# Mergen_Telemetri_Ate_leme.net
KiCad netlist of a schematic drawn in EAGLE
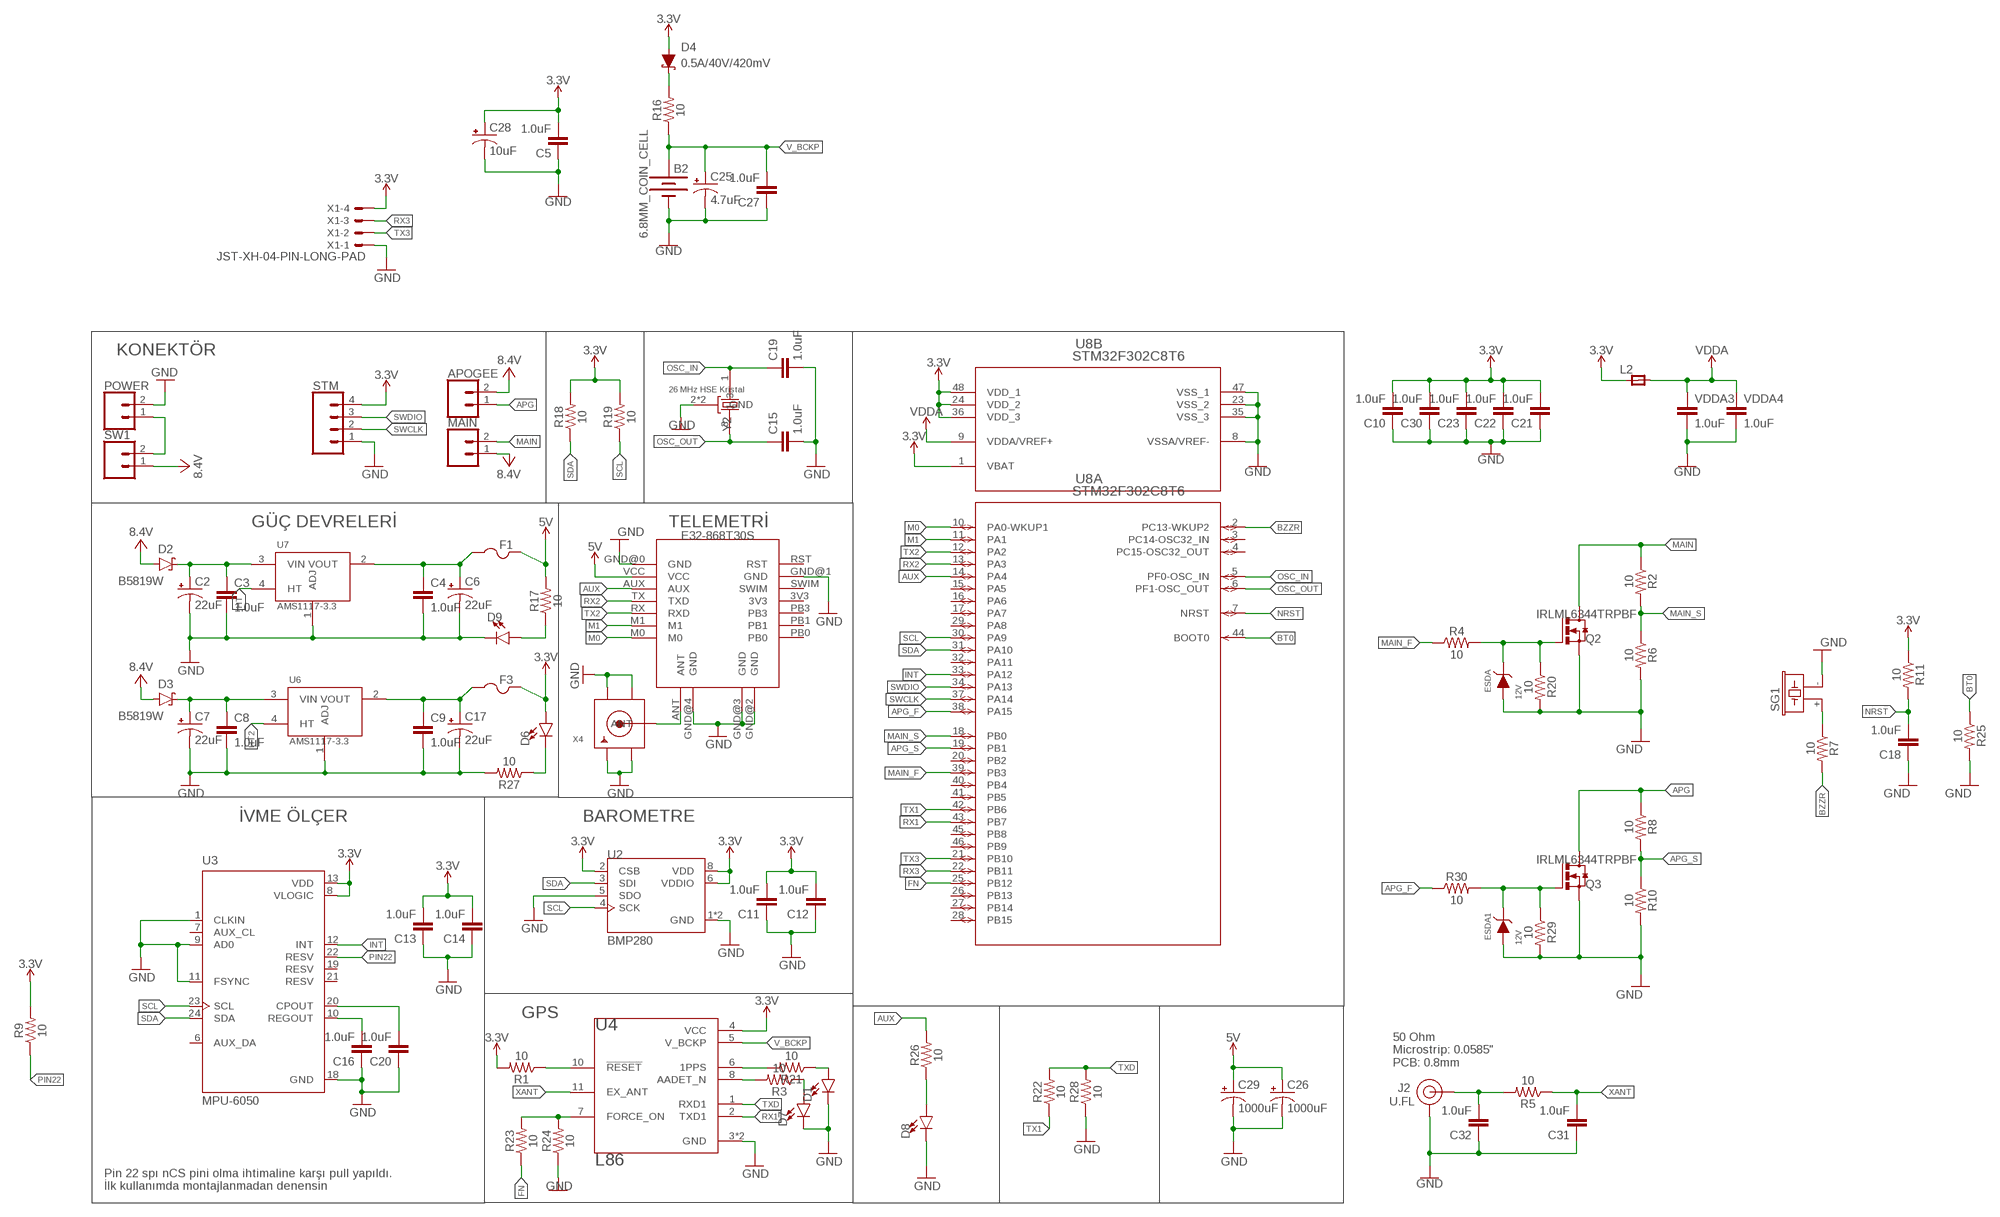
[diagram p0: schematic, sheet 1]

(export (version "E")
  (design (tool "Eeschema 10.0.6"))
  (components
    (comp (ref "APOGEE")
      (value "CONN_023.5MM-NO_SILK")
      (footprint "eagle-import:SCREWTERMINAL-3.5MM-2-NS")
      (libsource (lib "eagle-import") (part "CONN_023.5MM-NO_SILK"))
    )
    (comp (ref "B2")
      (value "6.8MM_COIN_CELL")
      (footprint "eagle-import:BATTCON-6.8MM")
      (libsource (lib "eagle-import") (part "BATTERY-6.8MM_SMD"))
    )
    (comp (ref "C2")
      (value "22uF")
      (footprint "eagle-import:EIA3528")
      (libsource (lib "eagle-import") (part "47UF-POLAR-EIA3528-10V-10%"))
    )
    (comp (ref "C3")
      (value "1.0uF")
      (footprint "eagle-import:1206")
      (libsource (lib "eagle-import") (part "1.0UF-1206-50V-10%"))
    )
    (comp (ref "C4")
      (value "1.0uF")
      (footprint "eagle-import:1206")
      (libsource (lib "eagle-import") (part "1.0UF-1206-50V-10%"))
    )
    (comp (ref "C5")
      (value "1.0uF")
      (footprint "eagle-import:1206")
      (libsource (lib "eagle-import") (part "1.0UF-1206-50V-10%"))
    )
    (comp (ref "C6")
      (value "22uF")
      (footprint "eagle-import:EIA3528")
      (libsource (lib "eagle-import") (part "47UF-POLAR-EIA3528-10V-10%"))
    )
    (comp (ref "C7")
      (value "22uF")
      (footprint "eagle-import:EIA3528")
      (libsource (lib "eagle-import") (part "47UF-POLAR-EIA3528-10V-10%"))
    )
    (comp (ref "C8")
      (value "1.0uF")
      (footprint "eagle-import:1206")
      (libsource (lib "eagle-import") (part "1.0UF-1206-50V-10%"))
    )
    (comp (ref "C9")
      (value "1.0uF")
      (footprint "eagle-import:1206")
      (libsource (lib "eagle-import") (part "1.0UF-1206-50V-10%"))
    )
    (comp (ref "C10")
      (value "1.0uF")
      (footprint "eagle-import:1206")
      (libsource (lib "eagle-import") (part "1.0UF-1206-50V-10%"))
    )
    (comp (ref "C11")
      (value "1.0uF")
      (footprint "eagle-import:1206")
      (libsource (lib "eagle-import") (part "1.0UF-1206-50V-10%"))
    )
    (comp (ref "C12")
      (value "1.0uF")
      (footprint "eagle-import:1206")
      (libsource (lib "eagle-import") (part "1.0UF-1206-50V-10%"))
    )
    (comp (ref "C13")
      (value "1.0uF")
      (footprint "eagle-import:1206")
      (libsource (lib "eagle-import") (part "1.0UF-1206-50V-10%"))
    )
    (comp (ref "C14")
      (value "1.0uF")
      (footprint "eagle-import:1206")
      (libsource (lib "eagle-import") (part "1.0UF-1206-50V-10%"))
    )
    (comp (ref "C15")
      (value "1.0uF")
      (footprint "eagle-import:1206")
      (libsource (lib "eagle-import") (part "1.0UF-1206-50V-10%"))
    )
    (comp (ref "C16")
      (value "1.0uF")
      (footprint "eagle-import:1206")
      (libsource (lib "eagle-import") (part "1.0UF-1206-50V-10%"))
    )
    (comp (ref "C17")
      (value "22uF")
      (footprint "eagle-import:EIA3528")
      (libsource (lib "eagle-import") (part "47UF-POLAR-EIA3528-10V-10%"))
    )
    (comp (ref "C18")
      (value "1.0uF")
      (footprint "eagle-import:1206")
      (libsource (lib "eagle-import") (part "1.0UF-1206-50V-10%"))
    )
    (comp (ref "C19")
      (value "1.0uF")
      (footprint "eagle-import:1206")
      (libsource (lib "eagle-import") (part "1.0UF-1206-50V-10%"))
    )
    (comp (ref "C20")
      (value "1.0uF")
      (footprint "eagle-import:1206")
      (libsource (lib "eagle-import") (part "1.0UF-1206-50V-10%"))
    )
    (comp (ref "C21")
      (value "1.0uF")
      (footprint "eagle-import:1206")
      (libsource (lib "eagle-import") (part "1.0UF-1206-50V-10%"))
    )
    (comp (ref "C22")
      (value "1.0uF")
      (footprint "eagle-import:1206")
      (libsource (lib "eagle-import") (part "1.0UF-1206-50V-10%"))
    )
    (comp (ref "C23")
      (value "1.0uF")
      (footprint "eagle-import:1206")
      (libsource (lib "eagle-import") (part "1.0UF-1206-50V-10%"))
    )
    (comp (ref "C25")
      (value "4.7uF")
      (footprint "eagle-import:EIA3528")
      (libsource (lib "eagle-import") (part "47UF-POLAR-EIA3528-10V-10%"))
    )
    (comp (ref "C26")
      (value "1000uF")
      (footprint "eagle-import:150CLZ-1010")
      (libsource (lib "eagle-import") (part "CPOL-US150CLZ-1010"))
    )
    (comp (ref "C27")
      (value "1.0uF")
      (footprint "eagle-import:1206")
      (libsource (lib "eagle-import") (part "1.0UF-1206-50V-10%"))
    )
    (comp (ref "C28")
      (value "10uF")
      (footprint "eagle-import:EIA3528")
      (libsource (lib "eagle-import") (part "47UF-POLAR-EIA3528-10V-10%"))
    )
    (comp (ref "C29")
      (value "1000uF")
      (footprint "eagle-import:150CLZ-1010")
      (libsource (lib "eagle-import") (part "CPOL-US150CLZ-1010"))
    )
    (comp (ref "C30")
      (value "1.0uF")
      (footprint "eagle-import:1206")
      (libsource (lib "eagle-import") (part "1.0UF-1206-50V-10%"))
    )
    (comp (ref "C31")
      (value "1.0uF")
      (footprint "eagle-import:1206")
      (libsource (lib "eagle-import") (part "1.0UF-1206-50V-10%"))
    )
    (comp (ref "C32")
      (value "1.0uF")
      (footprint "eagle-import:1206")
      (libsource (lib "eagle-import") (part "1.0UF-1206-50V-10%"))
    )
    (comp (ref "D1")
      (value "LED1206")
      (footprint "eagle-import:LED-1206")
      (libsource (lib "eagle-import") (part "LED1206"))
    )
    (comp (ref "D2")
      (value "B5819W")
      (footprint "eagle-import:SODFL3718X115")
      (fields (field (name "MANUFACTURER") "ON Semiconductor") (field (name "MPN") "MBR0520LT1G"))
      (libsource (lib "eagle-import") (part "SCHOTTKY_DO-219MBR0520LT1G"))
    )
    (comp (ref "D3")
      (value "B5819W")
      (footprint "eagle-import:SODFL3718X115")
      (fields (field (name "MANUFACTURER") "ON Semiconductor") (field (name "MPN") "MBR0520LT1G"))
      (libsource (lib "eagle-import") (part "SCHOTTKY_DO-219MBR0520LT1G"))
    )
    (comp (ref "D4")
      (value "0.5A/40V/420mV")
      (footprint "eagle-import:SOD-323")
      (libsource (lib "eagle-import") (part "DIODE-SCHOTTKY-PMEG4005EJ"))
    )
    (comp (ref "D6")
      (value "LED1206")
      (footprint "eagle-import:LED-1206")
      (libsource (lib "eagle-import") (part "LED1206"))
    )
    (comp (ref "D7")
      (value "LED1206")
      (footprint "eagle-import:LED-1206")
      (libsource (lib "eagle-import") (part "LED1206"))
    )
    (comp (ref "D8")
      (value "LED1206")
      (footprint "eagle-import:LED-1206")
      (libsource (lib "eagle-import") (part "LED1206"))
    )
    (comp (ref "D9")
      (value "LED1206")
      (footprint "eagle-import:LED-1206")
      (libsource (lib "eagle-import") (part "LED1206"))
    )
    (comp (ref "ESDA")
      (value "12V")
      (footprint "eagle-import:WE-TVSP_DO-214AC_UNIDIRECTIONAL")
      (libsource (lib "eagle-import") (part "WE-TVSP_DO-214AC_400W_UNI_824500102"))
    )
    (comp (ref "ESDA1")
      (value "12V")
      (footprint "eagle-import:WE-TVSP_DO-214AC_UNIDIRECTIONAL")
      (libsource (lib "eagle-import") (part "WE-TVSP_DO-214AC_400W_UNI_824500102"))
    )
    (comp (ref "F1")
      (value "1A")
      (footprint "eagle-import:R1206")
      (libsource (lib "eagle-import") (part "PTCFUSE-1206"))
    )
    (comp (ref "F3")
      (value "0.75A")
      (footprint "eagle-import:R1206")
      (libsource (lib "eagle-import") (part "PTCFUSE-1206"))
    )
    (comp (ref "J2")
      (value "U.FL")
      (footprint "eagle-import:U.FL")
      (libsource (lib "eagle-import") (part "U.FL2PIN"))
    )
    (comp (ref "L2")
      (value "RC-MASTER-SMD_FB_1206MP")
      (footprint "eagle-import:RC-MASTER-SMD_L1206MP")
      (libsource (lib "eagle-import") (part "RC-MASTER-SMD_FB_1206MP"))
    )
    (comp (ref "MAIN")
      (value "CONN_023.5MM-NO_SILK")
      (footprint "eagle-import:SCREWTERMINAL-3.5MM-2-NS")
      (libsource (lib "eagle-import") (part "CONN_023.5MM-NO_SILK"))
    )
    (comp (ref "POWER")
      (value "CONN_023.5MM-NO_SILK")
      (footprint "eagle-import:SCREWTERMINAL-3.5MM-2-NS")
      (libsource (lib "eagle-import") (part "CONN_023.5MM-NO_SILK"))
    )
    (comp (ref "Q2")
      (value "IRLML6344TRPBF")
      (footprint "eagle-import:SOT23")
      (fields (field (name "MF") "Infineon"))
      (libsource (lib "eagle-import") (part "IRLML6344TRPBF"))
    )
    (comp (ref "Q3")
      (value "IRLML6344TRPBF")
      (footprint "eagle-import:SOT23")
      (fields (field (name "MF") "Infineon"))
      (libsource (lib "eagle-import") (part "IRLML6344TRPBF"))
    )
    (comp (ref "R1")
      (value "10")
      (footprint "eagle-import:1206")
      (libsource (lib "eagle-import") (part "10OHM-1206-1/4W-1%"))
    )
    (comp (ref "R2")
      (value "10")
      (footprint "eagle-import:1206")
      (libsource (lib "eagle-import") (part "10OHM-1206-1/4W-1%"))
    )
    (comp (ref "R3")
      (value "10")
      (footprint "eagle-import:1206")
      (libsource (lib "eagle-import") (part "10OHM-1206-1/4W-1%"))
    )
    (comp (ref "R4")
      (value "10")
      (footprint "eagle-import:1206")
      (libsource (lib "eagle-import") (part "10OHM-1206-1/4W-1%"))
    )
    (comp (ref "R5")
      (value "10")
      (footprint "eagle-import:1206")
      (libsource (lib "eagle-import") (part "10OHM-1206-1/4W-1%"))
    )
    (comp (ref "R6")
      (value "10")
      (footprint "eagle-import:1206")
      (libsource (lib "eagle-import") (part "10OHM-1206-1/4W-1%"))
    )
    (comp (ref "R7")
      (value "10")
      (footprint "eagle-import:1206")
      (libsource (lib "eagle-import") (part "10OHM-1206-1/4W-1%"))
    )
    (comp (ref "R8")
      (value "10")
      (footprint "eagle-import:1206")
      (libsource (lib "eagle-import") (part "10OHM-1206-1/4W-1%"))
    )
    (comp (ref "R9")
      (value "10")
      (footprint "eagle-import:1206")
      (libsource (lib "eagle-import") (part "10OHM-1206-1/4W-1%"))
    )
    (comp (ref "R10")
      (value "10")
      (footprint "eagle-import:1206")
      (libsource (lib "eagle-import") (part "10OHM-1206-1/4W-1%"))
    )
    (comp (ref "R11")
      (value "10")
      (footprint "eagle-import:1206")
      (libsource (lib "eagle-import") (part "10OHM-1206-1/4W-1%"))
    )
    (comp (ref "R16")
      (value "10")
      (footprint "eagle-import:1206")
      (libsource (lib "eagle-import") (part "10OHM-1206-1/4W-1%"))
    )
    (comp (ref "R17")
      (value "10")
      (footprint "eagle-import:1206")
      (libsource (lib "eagle-import") (part "10OHM-1206-1/4W-1%"))
    )
    (comp (ref "R18")
      (value "10")
      (footprint "eagle-import:1206")
      (libsource (lib "eagle-import") (part "10OHM-1206-1/4W-1%"))
    )
    (comp (ref "R19")
      (value "10")
      (footprint "eagle-import:1206")
      (libsource (lib "eagle-import") (part "10OHM-1206-1/4W-1%"))
    )
    (comp (ref "R20")
      (value "10")
      (footprint "eagle-import:1206")
      (libsource (lib "eagle-import") (part "10OHM-1206-1/4W-1%"))
    )
    (comp (ref "R21")
      (value "10")
      (footprint "eagle-import:1206")
      (libsource (lib "eagle-import") (part "10OHM-1206-1/4W-1%"))
    )
    (comp (ref "R22")
      (value "10")
      (footprint "eagle-import:1206")
      (libsource (lib "eagle-import") (part "10OHM-1206-1/4W-1%"))
    )
    (comp (ref "R23")
      (value "10")
      (footprint "eagle-import:1206")
      (libsource (lib "eagle-import") (part "10OHM-1206-1/4W-1%"))
    )
    (comp (ref "R24")
      (value "10")
      (footprint "eagle-import:1206")
      (libsource (lib "eagle-import") (part "10OHM-1206-1/4W-1%"))
    )
    (comp (ref "R25")
      (value "10")
      (footprint "eagle-import:1206")
      (libsource (lib "eagle-import") (part "10OHM-1206-1/4W-1%"))
    )
    (comp (ref "R26")
      (value "10")
      (footprint "eagle-import:1206")
      (libsource (lib "eagle-import") (part "10OHM-1206-1/4W-1%"))
    )
    (comp (ref "R27")
      (value "10")
      (footprint "eagle-import:1206")
      (libsource (lib "eagle-import") (part "10OHM-1206-1/4W-1%"))
    )
    (comp (ref "R28")
      (value "10")
      (footprint "eagle-import:1206")
      (libsource (lib "eagle-import") (part "10OHM-1206-1/4W-1%"))
    )
    (comp (ref "R29")
      (value "10")
      (footprint "eagle-import:1206")
      (libsource (lib "eagle-import") (part "10OHM-1206-1/4W-1%"))
    )
    (comp (ref "R30")
      (value "10")
      (footprint "eagle-import:1206")
      (libsource (lib "eagle-import") (part "10OHM-1206-1/4W-1%"))
    )
    (comp (ref "SG1")
      (value "F/CM12P")
      (footprint "eagle-import:F_CM12P")
      (libsource (lib "eagle-import") (part "F/CM12P"))
    )
    (comp (ref "STM")
      (value "CONN_04")
      (footprint "eagle-import:1X04")
      (libsource (lib "eagle-import") (part "CONN_04"))
    )
    (comp (ref "SW1")
      (value "CONN_023.5MM-NO_SILK")
      (footprint "eagle-import:SCREWTERMINAL-3.5MM-2-NS")
      (libsource (lib "eagle-import") (part "CONN_023.5MM-NO_SILK"))
    )
    (comp (ref "U2")
      (value "BMP280")
      (footprint "eagle-import:XDCR_BMP280")
      (fields (field (name "MF") "Bosch"))
      (libsource (lib "eagle-import") (part "BMP280"))
    )
    (comp (ref "U3")
      (value "MPU-6050")
      (footprint "eagle-import:QFN50P400X400X95-24N")
      (fields (field (name "MF") "TDK InvenSense"))
      (libsource (lib "eagle-import") (part "MPU-6050"))
    )
    (comp (ref "U4")
      (value "L86")
      (footprint "eagle-import:XCVR_L86")
      (fields (field (name "MF") "Quectel"))
      (libsource (lib "eagle-import") (part "L86"))
    )
    (comp (ref "U5")
      (value "E32-868T30S")
      (footprint "eagle-import:E32-868T30S")
      (libsource (lib "eagle-import") (part "E32-868T30S"))
    )
    (comp (ref "U6")
      (value "AMS1117-3.3")
      (footprint "eagle-import:SOT229P700X180-4N")
      (fields (field (name "MF") "Advanced Monolithic Systems"))
      (libsource (lib "eagle-import") (part "AMS1117-3.3"))
    )
    (comp (ref "U7")
      (value "AMS1117-3.3")
      (footprint "eagle-import:SOT229P700X180-4N")
      (fields (field (name "MF") "Advanced Monolithic Systems"))
      (libsource (lib "eagle-import") (part "AMS1117-3.3"))
    )
    (comp (ref "U8")
      (value "STM32F302C8T6")
      (footprint "eagle-import:LQFP48-7X7MM")
      (fields (field (name "COPYRIGHT") "Copyright (C) 2018 Accelerated Designs. All rights reserved"))
      (libsource (lib "eagle-import") (part "STM32F302C8T6"))
    )
    (comp (ref "VDDA3")
      (value "1.0uF")
      (footprint "eagle-import:1206")
      (libsource (lib "eagle-import") (part "1.0UF-1206-50V-10%"))
    )
    (comp (ref "VDDA4")
      (value "1.0uF")
      (footprint "eagle-import:1206")
      (libsource (lib "eagle-import") (part "1.0UF-1206-50V-10%"))
    )
    (comp (ref "X1")
      (value "JST-XH-04-PIN-LONG-PAD")
      (footprint "eagle-import:JST-XH-04-PACKAGE-LONG-PAD")
      (libsource (lib "eagle-import") (part "JST-XH-04-PIN-LONG-PAD"))
    )
    (comp (ref "X4")
      (value "SMACONNECTOR")
      (footprint "eagle-import:SMA90_DIP")
      (libsource (lib "eagle-import") (part "SMACONNECTOR"))
    )
    (comp (ref "Y2")
      (value "ABM3B-26.000MHZ-10-1-U-T")
      (footprint "eagle-import:OSCCC500X320X110-4N")
      (fields (field (name "MF") "Abracon"))
      (libsource (lib "eagle-import") (part "ABM3B-26.000MHZ-10-1-U-T"))
    )
  )
  (nets
    (net (code "1") (name "3.3V") (class "Default")
      (node (ref "C10") (pin "2") (pinfunction "2_2") (pintype "passive"))
      (node (ref "C11") (pin "2") (pinfunction "2_2") (pintype "passive"))
      (node (ref "C12") (pin "2") (pinfunction "2_2") (pintype "passive"))
      (node (ref "C13") (pin "2") (pinfunction "2_2") (pintype "passive"))
      (node (ref "C14") (pin "2") (pinfunction "2_2") (pintype "passive"))
      (node (ref "C21") (pin "2") (pinfunction "2_2") (pintype "passive"))
      (node (ref "C22") (pin "2") (pinfunction "2_2") (pintype "passive"))
      (node (ref "C23") (pin "2") (pinfunction "2_2") (pintype "passive"))
      (node (ref "C28") (pin "A") (pinfunction "+_A") (pintype "passive"))
      (node (ref "C30") (pin "2") (pinfunction "2_2") (pintype "passive"))
      (node (ref "C5") (pin "2") (pinfunction "2_2") (pintype "passive"))
      (node (ref "D4") (pin "A") (pinfunction "A_A") (pintype "passive"))
      (node (ref "D6") (pin "A") (pinfunction "A_A") (pintype "passive"))
      (node (ref "F3") (pin "2") (pinfunction "2_2") (pintype "passive"))
      (node (ref "L2") (pin "1") (pinfunction "1_1") (pintype "passive"))
      (node (ref "R1") (pin "2") (pinfunction "2_2") (pintype "passive"))
      (node (ref "R11") (pin "1") (pinfunction "1_1") (pintype "passive"))
      (node (ref "R18") (pin "2") (pinfunction "2_2") (pintype "passive"))
      (node (ref "R19") (pin "2") (pinfunction "2_2") (pintype "passive"))
      (node (ref "R9") (pin "2") (pinfunction "2_2") (pintype "passive"))
      (node (ref "STM") (pin "4") (pinfunction "4_4") (pintype "passive"))
      (node (ref "U2") (pin "2") (pinfunction "CSB_2") (pintype "input"))
      (node (ref "U2") (pin "6") (pinfunction "VDDIO_6") (pintype "power_in"))
      (node (ref "U2") (pin "8") (pinfunction "VDD_8") (pintype "power_in"))
      (node (ref "U3") (pin "13") (pinfunction "VDD_13") (pintype "power_in"))
      (node (ref "U3") (pin "8") (pinfunction "VLOGIC_8") (pintype "power_in"))
      (node (ref "U4") (pin "4") (pinfunction "VCC_4") (pintype "power_in"))
      (node (ref "U8") (pin "1") (pinfunction "VBAT_1") (pintype "power_in"))
      (node (ref "U8") (pin "24") (pinfunction "VDD_2_24") (pintype "power_in"))
      (node (ref "U8") (pin "36") (pinfunction "VDD_3_36") (pintype "power_in"))
      (node (ref "U8") (pin "48") (pinfunction "VDD_1_48") (pintype "power_in"))
      (node (ref "X1") (pin "4") (pinfunction "S_4") (pintype "passive"))
    )
    (net (code "2") (name "5V") (class "Default")
      (node (ref "C26") (pin "+") (pinfunction "+_+") (pintype "passive"))
      (node (ref "C29") (pin "+") (pinfunction "+_+") (pintype "passive"))
      (node (ref "F1") (pin "2") (pinfunction "2_2") (pintype "passive"))
      (node (ref "R17") (pin "2") (pinfunction "2_2") (pintype "passive"))
      (node (ref "U5") (pin "VCC") (pinfunction "VCC_VCC") (pintype "bidirectional"))
    )
    (net (code "3") (name "8.4V") (class "Default")
      (node (ref "APOGEE") (pin "2") (pinfunction "2_2") (pintype "passive"))
      (node (ref "D2") (pin "2") (pinfunction "A_2") (pintype "passive"))
      (node (ref "D3") (pin "2") (pinfunction "A_2") (pintype "passive"))
      (node (ref "MAIN") (pin "1") (pinfunction "1_1") (pintype "passive"))
      (node (ref "SW1") (pin "1") (pinfunction "1_1") (pintype "passive"))
    )
    (net (code "4") (name "APG") (class "Default")
      (node (ref "APOGEE") (pin "1") (pinfunction "1_1") (pintype "passive"))
      (node (ref "Q3") (pin "3") (pinfunction "D_3") (pintype "passive"))
      (node (ref "R8") (pin "1") (pinfunction "1_1") (pintype "passive"))
    )
    (net (code "5") (name "APG_F") (class "Default")
      (node (ref "R30") (pin "1") (pinfunction "1_1") (pintype "passive"))
      (node (ref "U8") (pin "38") (pinfunction "PA15_38") (pintype "bidirectional"))
    )
    (net (code "6") (name "APG_S") (class "Default")
      (node (ref "R10") (pin "1") (pinfunction "1_1") (pintype "passive"))
      (node (ref "R8") (pin "2") (pinfunction "2_2") (pintype "passive"))
      (node (ref "U8") (pin "19") (pinfunction "PB1_19") (pintype "bidirectional"))
    )
    (net (code "7") (name "AUX") (class "Default")
      (node (ref "R26") (pin "2") (pinfunction "2_2") (pintype "passive"))
      (node (ref "U5") (pin "AUX") (pinfunction "AUX_AUX") (pintype "bidirectional"))
      (node (ref "U8") (pin "14") (pinfunction "PA4_14") (pintype "bidirectional"))
    )
    (net (code "8") (name "BT0") (class "Default")
      (node (ref "R25") (pin "1") (pinfunction "1_1") (pintype "passive"))
      (node (ref "U8") (pin "44") (pinfunction "BOOT0_44") (pintype "input"))
    )
    (net (code "9") (name "BZZR") (class "Default")
      (node (ref "R7") (pin "2") (pinfunction "2_2") (pintype "passive"))
      (node (ref "U8") (pin "2") (pinfunction "PC13-WKUP2_2") (pintype "bidirectional"))
    )
    (net (code "10") (name "FN") (class "Default")
      (node (ref "R23") (pin "1") (pinfunction "1_1") (pintype "passive"))
      (node (ref "U8") (pin "25") (pinfunction "PB12_25") (pintype "bidirectional"))
    )
    (net (code "11") (name "GND") (class "Default")
      (node (ref "B2") (pin "-") (pinfunction "-_-") (pintype "power_in"))
      (node (ref "C10") (pin "1") (pinfunction "1_1") (pintype "passive"))
      (node (ref "C11") (pin "1") (pinfunction "1_1") (pintype "passive"))
      (node (ref "C12") (pin "1") (pinfunction "1_1") (pintype "passive"))
      (node (ref "C13") (pin "1") (pinfunction "1_1") (pintype "passive"))
      (node (ref "C14") (pin "1") (pinfunction "1_1") (pintype "passive"))
      (node (ref "C15") (pin "2") (pinfunction "2_2") (pintype "passive"))
      (node (ref "C16") (pin "1") (pinfunction "1_1") (pintype "passive"))
      (node (ref "C17") (pin "C") (pinfunction "-_C") (pintype "passive"))
      (node (ref "C18") (pin "1") (pinfunction "1_1") (pintype "passive"))
      (node (ref "C19") (pin "2") (pinfunction "2_2") (pintype "passive"))
      (node (ref "C2") (pin "C") (pinfunction "-_C") (pintype "passive"))
      (node (ref "C20") (pin "1") (pinfunction "1_1") (pintype "passive"))
      (node (ref "C21") (pin "1") (pinfunction "1_1") (pintype "passive"))
      (node (ref "C22") (pin "1") (pinfunction "1_1") (pintype "passive"))
      (node (ref "C23") (pin "1") (pinfunction "1_1") (pintype "passive"))
      (node (ref "C25") (pin "C") (pinfunction "-_C") (pintype "passive"))
      (node (ref "C26") (pin "-") (pinfunction "-_-") (pintype "passive"))
      (node (ref "C27") (pin "1") (pinfunction "1_1") (pintype "passive"))
      (node (ref "C28") (pin "C") (pinfunction "-_C") (pintype "passive"))
      (node (ref "C29") (pin "-") (pinfunction "-_-") (pintype "passive"))
      (node (ref "C3") (pin "2") (pinfunction "2_2") (pintype "passive"))
      (node (ref "C30") (pin "1") (pinfunction "1_1") (pintype "passive"))
      (node (ref "C31") (pin "1") (pinfunction "1_1") (pintype "passive"))
      (node (ref "C32") (pin "1") (pinfunction "1_1") (pintype "passive"))
      (node (ref "C4") (pin "2") (pinfunction "2_2") (pintype "passive"))
      (node (ref "C5") (pin "1") (pinfunction "1_1") (pintype "passive"))
      (node (ref "C6") (pin "C") (pinfunction "-_C") (pintype "passive"))
      (node (ref "C7") (pin "C") (pinfunction "-_C") (pintype "passive"))
      (node (ref "C8") (pin "2") (pinfunction "2_2") (pintype "passive"))
      (node (ref "C9") (pin "2") (pinfunction "2_2") (pintype "passive"))
      (node (ref "D1") (pin "C") (pinfunction "C_C") (pintype "passive"))
      (node (ref "D7") (pin "C") (pinfunction "C_C") (pintype "passive"))
      (node (ref "D8") (pin "C") (pinfunction "C_C") (pintype "passive"))
      (node (ref "D9") (pin "C") (pinfunction "C_C") (pintype "passive"))
      (node (ref "ESDA") (pin "2") (pinfunction "A_2") (pintype "passive"))
      (node (ref "ESDA1") (pin "2") (pinfunction "A_2") (pintype "passive"))
      (node (ref "J2") (pin "1") (pinfunction "GND_1") (pintype "bidirectional"))
      (node (ref "J2") (pin "2") (pinfunction "GND_2") (pintype "bidirectional"))
      (node (ref "POWER") (pin "2") (pinfunction "2_2") (pintype "passive"))
      (node (ref "Q2") (pin "2") (pinfunction "S_2") (pintype "passive"))
      (node (ref "Q3") (pin "2") (pinfunction "S_2") (pintype "passive"))
      (node (ref "R10") (pin "2") (pinfunction "2_2") (pintype "passive"))
      (node (ref "R20") (pin "2") (pinfunction "2_2") (pintype "passive"))
      (node (ref "R24") (pin "1") (pinfunction "1_1") (pintype "passive"))
      (node (ref "R25") (pin "2") (pinfunction "2_2") (pintype "passive"))
      (node (ref "R27") (pin "2") (pinfunction "2_2") (pintype "passive"))
      (node (ref "R28") (pin "1") (pinfunction "1_1") (pintype "passive"))
      (node (ref "R29") (pin "2") (pinfunction "2_2") (pintype "passive"))
      (node (ref "R6") (pin "2") (pinfunction "2_2") (pintype "passive"))
      (node (ref "SG1") (pin "-") (pinfunction "2_-") (pintype "passive"))
      (node (ref "STM") (pin "1") (pinfunction "1_1") (pintype "passive"))
      (node (ref "U2") (pin "1") (pinfunction "GND_1") (pintype "power_in"))
      (node (ref "U2") (pin "5") (pinfunction "SDO_5") (pintype "bidirectional"))
      (node (ref "U2") (pin "7") (pinfunction "GND_7") (pintype "power_in"))
      (node (ref "U3") (pin "1") (pinfunction "CLKIN_1") (pintype "input"))
      (node (ref "U3") (pin "11") (pinfunction "FSYNC_11") (pintype "input"))
      (node (ref "U3") (pin "18") (pinfunction "GND_18") (pintype "power_in"))
      (node (ref "U3") (pin "9") (pinfunction "AD0_9") (pintype "input"))
      (node (ref "U4") (pin "12") (pinfunction "GND_12") (pintype "passive"))
      (node (ref "U4") (pin "3") (pinfunction "GND_3") (pintype "passive"))
      (node (ref "U5") (pin "GND@0") (pinfunction "GND_GND@0") (pintype "bidirectional"))
      (node (ref "U5") (pin "GND@1") (pinfunction "GND_GND@1") (pintype "bidirectional"))
      (node (ref "U5") (pin "GND@2") (pinfunction "GND_GND@2") (pintype "bidirectional"))
      (node (ref "U5") (pin "GND@3") (pinfunction "GND_GND@3") (pintype "bidirectional"))
      (node (ref "U5") (pin "GND@4") (pinfunction "GND_GND@4") (pintype "bidirectional"))
      (node (ref "U6") (pin "1") (pinfunction "ADJ_1") (pintype "power_in"))
      (node (ref "U7") (pin "1") (pinfunction "ADJ_1") (pintype "power_in"))
      (node (ref "U8") (pin "23") (pinfunction "VSS_2_23") (pintype "power_in"))
      (node (ref "U8") (pin "35") (pinfunction "VSS_3_35") (pintype "power_in"))
      (node (ref "U8") (pin "47") (pinfunction "VSS_1_47") (pintype "power_in"))
      (node (ref "U8") (pin "8") (pinfunction "VSSA/VREF-_8") (pintype "power_in"))
      (node (ref "VDDA3") (pin "2") (pinfunction "2_2") (pintype "passive"))
      (node (ref "VDDA4") (pin "2") (pinfunction "2_2") (pintype "passive"))
      (node (ref "X1") (pin "1") (pinfunction "S_1") (pintype "passive"))
      (node (ref "X4") (pin "GND1") (pinfunction "GND1_GND1") (pintype "power_in"))
      (node (ref "X4") (pin "GND2") (pinfunction "GND2_GND2") (pintype "power_in"))
      (node (ref "X4") (pin "GND3") (pinfunction "GND3_GND3") (pintype "power_in"))
      (node (ref "X4") (pin "GND4") (pinfunction "GND4_GND4") (pintype "power_in"))
      (node (ref "Y2") (pin "2") (pinfunction "GND_2") (pintype "passive"))
      (node (ref "Y2") (pin "4") (pinfunction "GND_4") (pintype "passive"))
    )
    (net (code "12") (name "HT") (class "Default")
      (node (ref "U7") (pin "4") (pinfunction "HT_4") (pintype "bidirectional"))
    )
    (net (code "13") (name "HT2") (class "Default")
      (node (ref "U6") (pin "4") (pinfunction "HT_4") (pintype "bidirectional"))
    )
    (net (code "14") (name "INT") (class "Default")
      (node (ref "U3") (pin "12") (pinfunction "INT_12") (pintype "output"))
      (node (ref "U8") (pin "33") (pinfunction "PA12_33") (pintype "bidirectional"))
    )
    (net (code "15") (name "M0") (class "Default")
      (node (ref "U5") (pin "M0") (pinfunction "M0_M0") (pintype "bidirectional"))
      (node (ref "U8") (pin "10") (pinfunction "PA0-WKUP1_10") (pintype "bidirectional"))
    )
    (net (code "16") (name "M1") (class "Default")
      (node (ref "U5") (pin "M1") (pinfunction "M1_M1") (pintype "bidirectional"))
      (node (ref "U8") (pin "11") (pinfunction "PA1_11") (pintype "bidirectional"))
    )
    (net (code "17") (name "MAIN") (class "Default")
      (node (ref "MAIN") (pin "2") (pinfunction "2_2") (pintype "passive"))
      (node (ref "Q2") (pin "3") (pinfunction "D_3") (pintype "passive"))
      (node (ref "R2") (pin "1") (pinfunction "1_1") (pintype "passive"))
    )
    (net (code "18") (name "MAIN_F") (class "Default")
      (node (ref "R4") (pin "1") (pinfunction "1_1") (pintype "passive"))
      (node (ref "U8") (pin "39") (pinfunction "PB3_39") (pintype "bidirectional"))
    )
    (net (code "19") (name "MAIN_S") (class "Default")
      (node (ref "R2") (pin "2") (pinfunction "2_2") (pintype "passive"))
      (node (ref "R6") (pin "1") (pinfunction "1_1") (pintype "passive"))
      (node (ref "U8") (pin "18") (pinfunction "PB0_18") (pintype "bidirectional"))
    )
    (net (code "20") (name "NRST") (class "Default")
      (node (ref "C18") (pin "2") (pinfunction "2_2") (pintype "passive"))
      (node (ref "R11") (pin "2") (pinfunction "2_2") (pintype "passive"))
      (node (ref "U8") (pin "7") (pinfunction "NRST_7") (pintype "bidirectional"))
    )
    (net (code "21") (name "Net-(C2-+)") (class "Default")
      (node (ref "C2") (pin "A") (pinfunction "+_A") (pintype "passive"))
      (node (ref "C3") (pin "1") (pinfunction "1_1") (pintype "passive"))
      (node (ref "D2") (pin "1") (pinfunction "C_1") (pintype "passive"))
      (node (ref "U7") (pin "3") (pinfunction "VIN_3") (pintype "input"))
    )
    (net (code "22") (name "Net-(C6-+)") (class "Default")
      (node (ref "C4") (pin "1") (pinfunction "1_1") (pintype "passive"))
      (node (ref "C6") (pin "A") (pinfunction "+_A") (pintype "passive"))
      (node (ref "F1") (pin "1") (pinfunction "1_1") (pintype "passive"))
      (node (ref "U7") (pin "2") (pinfunction "VOUT_2") (pintype "output"))
    )
    (net (code "23") (name "Net-(C7-+)") (class "Default")
      (node (ref "C7") (pin "A") (pinfunction "+_A") (pintype "passive"))
      (node (ref "C8") (pin "1") (pinfunction "1_1") (pintype "passive"))
      (node (ref "D3") (pin "1") (pinfunction "C_1") (pintype "passive"))
      (node (ref "U6") (pin "3") (pinfunction "VIN_3") (pintype "input"))
    )
    (net (code "24") (name "Net-(C17-+)") (class "Default")
      (node (ref "C17") (pin "A") (pinfunction "+_A") (pintype "passive"))
      (node (ref "C9") (pin "1") (pinfunction "1_1") (pintype "passive"))
      (node (ref "F3") (pin "1") (pinfunction "1_1") (pintype "passive"))
      (node (ref "U6") (pin "2") (pinfunction "VOUT_2") (pintype "output"))
    )
    (net (code "25") (name "Net-(D1-PadA)") (class "Default")
      (node (ref "D1") (pin "A") (pinfunction "A_A") (pintype "passive"))
      (node (ref "R21") (pin "1") (pinfunction "1_1") (pintype "passive"))
    )
    (net (code "26") (name "Net-(D4-PadC)") (class "Default")
      (node (ref "D4") (pin "C") (pinfunction "C_C") (pintype "passive"))
      (node (ref "R16") (pin "2") (pinfunction "2_2") (pintype "passive"))
    )
    (net (code "27") (name "Net-(D6-PadC)") (class "Default")
      (node (ref "D6") (pin "C") (pinfunction "C_C") (pintype "passive"))
      (node (ref "R27") (pin "1") (pinfunction "1_1") (pintype "passive"))
    )
    (net (code "28") (name "Net-(D7-PadA)") (class "Default")
      (node (ref "D7") (pin "A") (pinfunction "A_A") (pintype "passive"))
      (node (ref "R3") (pin "1") (pinfunction "1_1") (pintype "passive"))
    )
    (net (code "29") (name "Net-(D8-PadA)") (class "Default")
      (node (ref "D8") (pin "A") (pinfunction "A_A") (pintype "passive"))
      (node (ref "R26") (pin "1") (pinfunction "1_1") (pintype "passive"))
    )
    (net (code "30") (name "Net-(D9-PadA)") (class "Default")
      (node (ref "D9") (pin "A") (pinfunction "A_A") (pintype "passive"))
      (node (ref "R17") (pin "1") (pinfunction "1_1") (pintype "passive"))
    )
    (net (code "31") (name "Net-(ESDA-C)") (class "Default")
      (node (ref "ESDA") (pin "1") (pinfunction "C_1") (pintype "passive"))
      (node (ref "Q2") (pin "1") (pinfunction "G_1") (pintype "passive"))
      (node (ref "R20") (pin "1") (pinfunction "1_1") (pintype "passive"))
      (node (ref "R4") (pin "2") (pinfunction "2_2") (pintype "passive"))
    )
    (net (code "32") (name "Net-(ESDA1-C)") (class "Default")
      (node (ref "ESDA1") (pin "1") (pinfunction "C_1") (pintype "passive"))
      (node (ref "Q3") (pin "1") (pinfunction "G_1") (pintype "passive"))
      (node (ref "R29") (pin "1") (pinfunction "1_1") (pintype "passive"))
      (node (ref "R30") (pin "2") (pinfunction "2_2") (pintype "passive"))
    )
    (net (code "33") (name "Net-(J2-SIGNAL)") (class "Default")
      (node (ref "C32") (pin "2") (pinfunction "2_2") (pintype "passive"))
      (node (ref "J2") (pin "FEED") (pinfunction "SIGNAL_FEED") (pintype "bidirectional"))
      (node (ref "R5") (pin "2") (pinfunction "2_2") (pintype "passive"))
    )
    (net (code "34") (name "Net-(POWER-Pad1)") (class "Default")
      (node (ref "POWER") (pin "1") (pinfunction "1_1") (pintype "passive"))
      (node (ref "SW1") (pin "2") (pinfunction "2_2") (pintype "passive"))
    )
    (net (code "35") (name "Net-(SG1-1)") (class "Default")
      (node (ref "R7") (pin "1") (pinfunction "1_1") (pintype "passive"))
      (node (ref "SG1") (pin "+") (pinfunction "1_+") (pintype "passive"))
    )
    (net (code "36") (name "Net-(U3-CPOUT)") (class "Default")
      (node (ref "C20") (pin "2") (pinfunction "2_2") (pintype "passive"))
      (node (ref "U3") (pin "20") (pinfunction "CPOUT_20") (pintype "passive"))
    )
    (net (code "37") (name "Net-(U3-REGOUT)") (class "Default")
      (node (ref "C16") (pin "2") (pinfunction "2_2") (pintype "passive"))
      (node (ref "U3") (pin "10") (pinfunction "REGOUT_10") (pintype "passive"))
    )
    (net (code "38") (name "Net-(U4-1PPS)") (class "Default")
      (node (ref "R21") (pin "2") (pinfunction "2_2") (pintype "passive"))
      (node (ref "U4") (pin "6") (pinfunction "1PPS_6") (pintype "output"))
    )
    (net (code "39") (name "Net-(U4-AADET_N)") (class "Default")
      (node (ref "R3") (pin "2") (pinfunction "2_2") (pintype "passive"))
      (node (ref "U4") (pin "8") (pinfunction "AADET_N_8") (pintype "output"))
    )
    (net (code "40") (name "Net-(U4-FORCE_ON)") (class "Default")
      (node (ref "R23") (pin "2") (pinfunction "2_2") (pintype "passive"))
      (node (ref "R24") (pin "2") (pinfunction "2_2") (pintype "passive"))
      (node (ref "U4") (pin "7") (pinfunction "FORCE_ON_7") (pintype "input"))
    )
    (net (code "41") (name "Net-(U4-~{RESET})") (class "Default")
      (node (ref "R1") (pin "1") (pinfunction "1_1") (pintype "passive"))
      (node (ref "U4") (pin "10") (pinfunction "~{RESET}_10") (pintype "input"))
    )
    (net (code "42") (name "Net-(X4-ANT)") (class "Default")
      (node (ref "U5") (pin "ANT") (pinfunction "ANT_ANT") (pintype "bidirectional"))
      (node (ref "X4") (pin "ANTENNA") (pinfunction "ANT_ANTENNA") (pintype "bidirectional"))
    )
    (net (code "43") (name "OSC_IN") (class "Default")
      (node (ref "C19") (pin "1") (pinfunction "1_1") (pintype "passive"))
      (node (ref "U8") (pin "5") (pinfunction "PF0-OSC_IN_5") (pintype "bidirectional"))
      (node (ref "Y2") (pin "1") (pinfunction "1_1") (pintype "passive"))
    )
    (net (code "44") (name "OSC_OUT") (class "Default")
      (node (ref "C15") (pin "1") (pinfunction "1_1") (pintype "passive"))
      (node (ref "U8") (pin "6") (pinfunction "PF1-OSC_OUT_6") (pintype "bidirectional"))
      (node (ref "Y2") (pin "3") (pinfunction "3_3") (pintype "passive"))
    )
    (net (code "45") (name "PIN22") (class "Default")
      (node (ref "R9") (pin "1") (pinfunction "1_1") (pintype "passive"))
      (node (ref "U3") (pin "22") (pinfunction "RESV_22") (pintype "passive"))
    )
    (net (code "46") (name "RX1") (class "Default")
      (node (ref "U4") (pin "2") (pinfunction "TXD1_2") (pintype "output"))
      (node (ref "U8") (pin "43") (pinfunction "PB7_43") (pintype "bidirectional"))
    )
    (net (code "47") (name "RX2") (class "Default")
      (node (ref "U5") (pin "TX") (pinfunction "TXD_TX") (pintype "bidirectional"))
      (node (ref "U8") (pin "13") (pinfunction "PA3_13") (pintype "bidirectional"))
    )
    (net (code "48") (name "RX3") (class "Default")
      (node (ref "U8") (pin "22") (pinfunction "PB11_22") (pintype "bidirectional"))
      (node (ref "X1") (pin "3") (pinfunction "S_3") (pintype "passive"))
    )
    (net (code "49") (name "SCL") (class "Default")
      (node (ref "R19") (pin "1") (pinfunction "1_1") (pintype "passive"))
      (node (ref "U2") (pin "4") (pinfunction "SCK_4") (pintype "input"))
      (node (ref "U3") (pin "23") (pinfunction "SCL_23") (pintype "input"))
      (node (ref "U8") (pin "30") (pinfunction "PA9_30") (pintype "bidirectional"))
    )
    (net (code "50") (name "SDA") (class "Default")
      (node (ref "R18") (pin "1") (pinfunction "1_1") (pintype "passive"))
      (node (ref "U2") (pin "3") (pinfunction "SDI_3") (pintype "bidirectional"))
      (node (ref "U3") (pin "24") (pinfunction "SDA_24") (pintype "bidirectional"))
      (node (ref "U8") (pin "31") (pinfunction "PA10_31") (pintype "bidirectional"))
    )
    (net (code "51") (name "SWCLK") (class "Default")
      (node (ref "STM") (pin "2") (pinfunction "2_2") (pintype "passive"))
      (node (ref "U8") (pin "37") (pinfunction "PA14_37") (pintype "bidirectional"))
    )
    (net (code "52") (name "SWDIO") (class "Default")
      (node (ref "STM") (pin "3") (pinfunction "3_3") (pintype "passive"))
      (node (ref "U8") (pin "34") (pinfunction "PA13_34") (pintype "bidirectional"))
    )
    (net (code "53") (name "TX1") (class "Default")
      (node (ref "R22") (pin "1") (pinfunction "1_1") (pintype "passive"))
      (node (ref "U8") (pin "42") (pinfunction "PB6_42") (pintype "bidirectional"))
    )
    (net (code "54") (name "TX2") (class "Default")
      (node (ref "U5") (pin "RX") (pinfunction "RXD_RX") (pintype "bidirectional"))
      (node (ref "U8") (pin "12") (pinfunction "PA2_12") (pintype "bidirectional"))
    )
    (net (code "55") (name "TX3") (class "Default")
      (node (ref "U8") (pin "21") (pinfunction "PB10_21") (pintype "bidirectional"))
      (node (ref "X1") (pin "2") (pinfunction "S_2") (pintype "passive"))
    )
    (net (code "56") (name "TXD") (class "Default")
      (node (ref "R22") (pin "2") (pinfunction "2_2") (pintype "passive"))
      (node (ref "R28") (pin "2") (pinfunction "2_2") (pintype "passive"))
      (node (ref "U4") (pin "1") (pinfunction "RXD1_1") (pintype "input"))
    )
    (net (code "57") (name "VDDA") (class "Default")
      (node (ref "L2") (pin "2") (pinfunction "2_2") (pintype "passive"))
      (node (ref "U8") (pin "9") (pinfunction "VDDA/VREF+_9") (pintype "power_in"))
      (node (ref "VDDA3") (pin "1") (pinfunction "1_1") (pintype "passive"))
      (node (ref "VDDA4") (pin "1") (pinfunction "1_1") (pintype "passive"))
    )
    (net (code "58") (name "V_BCKP") (class "Default")
      (node (ref "B2") (pin "+") (pinfunction "+_+") (pintype "power_in"))
      (node (ref "C25") (pin "A") (pinfunction "+_A") (pintype "passive"))
      (node (ref "C27") (pin "2") (pinfunction "2_2") (pintype "passive"))
      (node (ref "R16") (pin "1") (pinfunction "1_1") (pintype "passive"))
      (node (ref "U4") (pin "5") (pinfunction "V_BCKP_5") (pintype "power_in"))
    )
    (net (code "59") (name "XANT") (class "Default")
      (node (ref "C31") (pin "2") (pinfunction "2_2") (pintype "passive"))
      (node (ref "R5") (pin "1") (pinfunction "1_1") (pintype "passive"))
      (node (ref "U4") (pin "11") (pinfunction "EX_ANT_11") (pintype "input"))
    )
    (net (code "60") (name "unconnected-(U3-AUX_CL-Pad7)") (class "Default")
      (node (ref "U3") (pin "7") (pinfunction "AUX_CL_7") (pintype "input"))
    )
    (net (code "61") (name "unconnected-(U3-AUX_DA-Pad6)") (class "Default")
      (node (ref "U3") (pin "6") (pinfunction "AUX_DA_6") (pintype "bidirectional"))
    )
    (net (code "62") (name "unconnected-(U3-RESV-Pad19)") (class "Default")
      (node (ref "U3") (pin "19") (pinfunction "RESV_19") (pintype "passive"))
    )
    (net (code "63") (name "unconnected-(U3-RESV-Pad21)") (class "Default")
      (node (ref "U3") (pin "21") (pinfunction "RESV_21") (pintype "passive"))
    )
    (net (code "64") (name "unconnected-(U5-Pad3V3)") (class "Default")
      (node (ref "U5") (pin "3V3") (pinfunction "3V3_3V3") (pintype "bidirectional"))
    )
    (net (code "65") (name "unconnected-(U5-PadPB0)") (class "Default")
      (node (ref "U5") (pin "PB0") (pinfunction "PB0_PB0") (pintype "bidirectional"))
    )
    (net (code "66") (name "unconnected-(U5-PadPB1)") (class "Default")
      (node (ref "U5") (pin "PB1") (pinfunction "PB1_PB1") (pintype "bidirectional"))
    )
    (net (code "67") (name "unconnected-(U5-PadPB3)") (class "Default")
      (node (ref "U5") (pin "PB3") (pinfunction "PB3_PB3") (pintype "bidirectional"))
    )
    (net (code "68") (name "unconnected-(U5-PadRST)") (class "Default")
      (node (ref "U5") (pin "RST") (pinfunction "RST_RST") (pintype "bidirectional"))
    )
    (net (code "69") (name "unconnected-(U5-PadSWIM)") (class "Default")
      (node (ref "U5") (pin "SWIM") (pinfunction "SWIM_SWIM") (pintype "bidirectional"))
    )
    (net (code "70") (name "unconnected-(U8A-PA5-Pad15)") (class "Default")
      (node (ref "U8") (pin "15") (pinfunction "PA5_15") (pintype "bidirectional"))
    )
    (net (code "71") (name "unconnected-(U8A-PA6-Pad16)") (class "Default")
      (node (ref "U8") (pin "16") (pinfunction "PA6_16") (pintype "bidirectional"))
    )
    (net (code "72") (name "unconnected-(U8A-PA7-Pad17)") (class "Default")
      (node (ref "U8") (pin "17") (pinfunction "PA7_17") (pintype "bidirectional"))
    )
    (net (code "73") (name "unconnected-(U8A-PA8-Pad29)") (class "Default")
      (node (ref "U8") (pin "29") (pinfunction "PA8_29") (pintype "bidirectional"))
    )
    (net (code "74") (name "unconnected-(U8A-PA11-Pad32)") (class "Default")
      (node (ref "U8") (pin "32") (pinfunction "PA11_32") (pintype "bidirectional"))
    )
    (net (code "75") (name "unconnected-(U8A-PB2-Pad20)") (class "Default")
      (node (ref "U8") (pin "20") (pinfunction "PB2_20") (pintype "bidirectional"))
    )
    (net (code "76") (name "unconnected-(U8A-PB4-Pad40)") (class "Default")
      (node (ref "U8") (pin "40") (pinfunction "PB4_40") (pintype "bidirectional"))
    )
    (net (code "77") (name "unconnected-(U8A-PB5-Pad41)") (class "Default")
      (node (ref "U8") (pin "41") (pinfunction "PB5_41") (pintype "bidirectional"))
    )
    (net (code "78") (name "unconnected-(U8A-PB8-Pad45)") (class "Default")
      (node (ref "U8") (pin "45") (pinfunction "PB8_45") (pintype "bidirectional"))
    )
    (net (code "79") (name "unconnected-(U8A-PB9-Pad46)") (class "Default")
      (node (ref "U8") (pin "46") (pinfunction "PB9_46") (pintype "bidirectional"))
    )
    (net (code "80") (name "unconnected-(U8A-PB13-Pad26)") (class "Default")
      (node (ref "U8") (pin "26") (pinfunction "PB13_26") (pintype "bidirectional"))
    )
    (net (code "81") (name "unconnected-(U8A-PB14-Pad27)") (class "Default")
      (node (ref "U8") (pin "27") (pinfunction "PB14_27") (pintype "bidirectional"))
    )
    (net (code "82") (name "unconnected-(U8A-PB15-Pad28)") (class "Default")
      (node (ref "U8") (pin "28") (pinfunction "PB15_28") (pintype "bidirectional"))
    )
    (net (code "83") (name "unconnected-(U8A-PC14-OSC32_IN-Pad3)") (class "Default")
      (node (ref "U8") (pin "3") (pinfunction "PC14-OSC32_IN_3") (pintype "bidirectional"))
    )
    (net (code "84") (name "unconnected-(U8A-PC15-OSC32_OUT-Pad4)") (class "Default")
      (node (ref "U8") (pin "4") (pinfunction "PC15-OSC32_OUT_4") (pintype "bidirectional"))
    )
  )
)
